# Tile1.net
KiCad netlist of a schematic drawn in Altium Designer
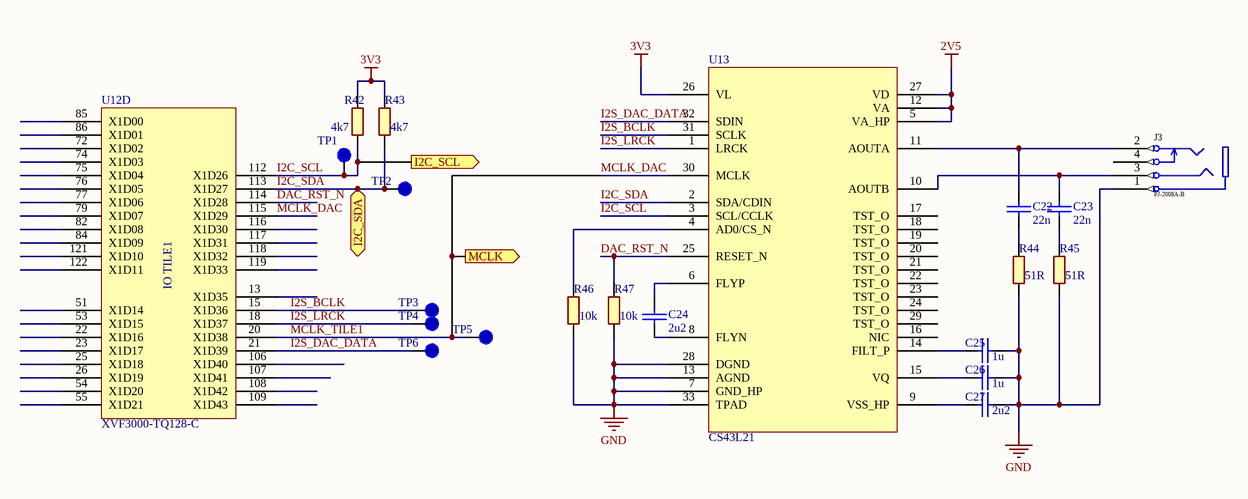
[diagram p0: Tile1.SchDoc]

(export (version "E")
  (design (tool "Eeschema 10.0.6"))
  (components
    (comp (ref "C22")
      (value "22n")
      (footprint "C0603")
      (description "Capacitor")
      (libsource (lib "Library") (part "CAP"))
    )
    (comp (ref "C23")
      (value "22n")
      (footprint "C0603")
      (description "Capacitor")
      (libsource (lib "Library") (part "CAP"))
    )
    (comp (ref "C24")
      (value "2u2")
      (footprint "C0603")
      (description "Capacitor")
      (libsource (lib "Library") (part "CAP"))
    )
    (comp (ref "C25")
      (value "1u")
      (footprint "C0603")
      (description "Capacitor")
      (libsource (lib "Library") (part "CAP"))
    )
    (comp (ref "C26")
      (value "1u")
      (footprint "C0603")
      (description "Capacitor")
      (libsource (lib "Library") (part "CAP"))
    )
    (comp (ref "C27")
      (value "2u2")
      (footprint "C0603")
      (description "Capacitor")
      (libsource (lib "Library") (part "CAP"))
    )
    (comp (ref "J3")
      (value "PJ-2008A-B")
      (footprint "PJ-2008A-B")
      (libsource (lib "Library") (part "PJ-2008A-B"))
    )
    (comp (ref "R42")
      (value "4k7")
      (footprint "R0603")
      (description "RES")
      (libsource (lib "Library") (part "R"))
    )
    (comp (ref "R43")
      (value "4k7")
      (footprint "R0603")
      (description "RES")
      (libsource (lib "Library") (part "R"))
    )
    (comp (ref "R44")
      (value "51R")
      (footprint "R0603")
      (description "RES")
      (libsource (lib "Library") (part "R"))
    )
    (comp (ref "R45")
      (value "51R")
      (footprint "R0603")
      (description "RES")
      (libsource (lib "Library") (part "R"))
    )
    (comp (ref "R46")
      (value "10k")
      (footprint "R0603")
      (description "RES")
      (libsource (lib "Library") (part "R"))
    )
    (comp (ref "R47")
      (value "10k")
      (footprint "R0603")
      (description "RES")
      (libsource (lib "Library") (part "R"))
    )
    (comp (ref "TP1") (value "TP") (footprint "TP1") (libsource (lib "Library") (part "TP")))
    (comp (ref "TP2") (value "TP") (footprint "TP1") (libsource (lib "Library") (part "TP")))
    (comp (ref "TP3") (value "TP") (footprint "TP1") (libsource (lib "Library") (part "TP")))
    (comp (ref "TP4") (value "TP") (footprint "TP1") (libsource (lib "Library") (part "TP")))
    (comp (ref "TP5") (value "TP") (footprint "TP1") (libsource (lib "Library") (part "TP")))
    (comp (ref "TP6") (value "TP") (footprint "TP1") (libsource (lib "Library") (part "TP")))
    (comp (ref "U12")
      (value "XVF3000-TQ128-C")
      (footprint "LQFP-128 - VSS")
      (libsource (lib "Library") (part "XVF3000-TQ128-C"))
    )
    (comp (ref "U13") (value "CS43L21") (footprint "QFN-32") (libsource (lib "Library") (part "CS43L21")))
  )
  (nets
    (net (code "1") (name "/DAC_RST_N") (class "Default")
      (node (ref "R47") (pin "2") (pinfunction "2_2") (pintype "passive"))
      (node (ref "U12") (pin "114") (pinfunction "X1D28_114") (pintype "passive"))
      (node (ref "U13") (pin "25") (pinfunction "RESET_N_25") (pintype "passive"))
    )
    (net (code "2") (name "/I2C_SCL") (class "Default")
      (node (ref "R42") (pin "1") (pinfunction "1_1") (pintype "passive"))
      (node (ref "TP1") (pin "1") (pinfunction "1_1") (pintype "passive"))
      (node (ref "U12") (pin "112") (pinfunction "X1D26_112") (pintype "passive"))
      (node (ref "U13") (pin "3") (pinfunction "SCL/CCLK_3") (pintype "passive"))
    )
    (net (code "3") (name "/I2C_SDA") (class "Default")
      (node (ref "R43") (pin "1") (pinfunction "1_1") (pintype "passive"))
      (node (ref "TP2") (pin "1") (pinfunction "1_1") (pintype "passive"))
      (node (ref "U12") (pin "113") (pinfunction "X1D27_113") (pintype "passive"))
      (node (ref "U13") (pin "2") (pinfunction "SDA/CDIN_2") (pintype "passive"))
    )
    (net (code "4") (name "/I2S_BCLK") (class "Default")
      (node (ref "TP3") (pin "1") (pinfunction "1_1") (pintype "passive"))
      (node (ref "U12") (pin "15") (pinfunction "X1D36_15") (pintype "passive"))
      (node (ref "U13") (pin "31") (pinfunction "SCLK_31") (pintype "passive"))
    )
    (net (code "5") (name "/I2S_DAC_DATA") (class "Default")
      (node (ref "TP6") (pin "1") (pinfunction "1_1") (pintype "passive"))
      (node (ref "U12") (pin "21") (pinfunction "X1D39_21") (pintype "passive"))
      (node (ref "U13") (pin "32") (pinfunction "SDIN_32") (pintype "passive"))
    )
    (net (code "6") (name "/I2S_LRCK") (class "Default")
      (node (ref "TP4") (pin "1") (pinfunction "1_1") (pintype "passive"))
      (node (ref "U12") (pin "18") (pinfunction "X1D37_18") (pintype "passive"))
      (node (ref "U13") (pin "1") (pinfunction "LRCK_1") (pintype "passive"))
    )
    (net (code "7") (name "/MCLK_DAC") (class "Default")
      (node (ref "TP5") (pin "1") (pinfunction "1_1") (pintype "passive"))
      (node (ref "U12") (pin "115") (pinfunction "X1D29_115") (pintype "passive"))
      (node (ref "U12") (pin "20") (pinfunction "X1D38_20") (pintype "passive"))
      (node (ref "U13") (pin "30") (pinfunction "MCLK_30") (pintype "passive"))
    )
    (net (code "8") (name "2V5") (class "Default")
      (node (ref "U13") (pin "12") (pinfunction "VA_12") (pintype "passive"))
      (node (ref "U13") (pin "27") (pinfunction "VD_27") (pintype "passive"))
      (node (ref "U13") (pin "5") (pinfunction "VA_HP_5") (pintype "passive"))
    )
    (net (code "9") (name "3V3") (class "Default")
      (node (ref "R42") (pin "2") (pinfunction "2_2") (pintype "passive"))
      (node (ref "R43") (pin "2") (pinfunction "2_2") (pintype "passive"))
      (node (ref "U13") (pin "26") (pinfunction "VL_26") (pintype "passive"))
    )
    (net (code "10") (name "GND") (class "Default")
      (node (ref "C25") (pin "2") (pinfunction "2_2") (pintype "passive"))
      (node (ref "C26") (pin "2") (pinfunction "2_2") (pintype "passive"))
      (node (ref "C27") (pin "2") (pinfunction "2_2") (pintype "passive"))
      (node (ref "J3") (pin "1") (pintype "output"))
      (node (ref "R44") (pin "1") (pinfunction "1_1") (pintype "passive"))
      (node (ref "R45") (pin "1") (pinfunction "1_1") (pintype "passive"))
      (node (ref "R46") (pin "1") (pinfunction "1_1") (pintype "passive"))
      (node (ref "R47") (pin "1") (pinfunction "1_1") (pintype "passive"))
      (node (ref "U13") (pin "13") (pinfunction "AGND_13") (pintype "passive"))
      (node (ref "U13") (pin "28") (pinfunction "DGND_28") (pintype "passive"))
      (node (ref "U13") (pin "33") (pinfunction "TPAD_33") (pintype "passive"))
      (node (ref "U13") (pin "7") (pinfunction "GND_HP_7") (pintype "passive"))
    )
    (net (code "11") (name "Net-(C22-Pad1)") (class "Default")
      (node (ref "C22") (pin "1") (pinfunction "1_1") (pintype "passive"))
      (node (ref "R44") (pin "2") (pinfunction "2_2") (pintype "passive"))
    )
    (net (code "12") (name "Net-(C23-Pad1)") (class "Default")
      (node (ref "C23") (pin "1") (pinfunction "1_1") (pintype "passive"))
      (node (ref "R45") (pin "2") (pinfunction "2_2") (pintype "passive"))
    )
    (net (code "13") (name "Net-(U13-AD0{slash}CS_N)") (class "Default")
      (node (ref "R46") (pin "2") (pinfunction "2_2") (pintype "passive"))
      (node (ref "U13") (pin "4") (pinfunction "AD0/CS_N_4") (pintype "passive"))
    )
    (net (code "14") (name "Net-(U13-AOUTA)") (class "Default")
      (node (ref "C22") (pin "2") (pinfunction "2_2") (pintype "passive"))
      (node (ref "J3") (pin "2") (pintype "output"))
      (node (ref "U13") (pin "11") (pinfunction "AOUTA_11") (pintype "passive"))
    )
    (net (code "15") (name "Net-(U13-AOUTB)") (class "Default")
      (node (ref "C23") (pin "2") (pinfunction "2_2") (pintype "passive"))
      (node (ref "J3") (pin "3") (pintype "output"))
      (node (ref "U13") (pin "10") (pinfunction "AOUTB_10") (pintype "passive"))
    )
    (net (code "16") (name "Net-(U13-FILT_P)") (class "Default")
      (node (ref "C25") (pin "1") (pinfunction "1_1") (pintype "passive"))
      (node (ref "U13") (pin "14") (pinfunction "FILT_P_14") (pintype "passive"))
    )
    (net (code "17") (name "Net-(U13-FLYN)") (class "Default")
      (node (ref "C24") (pin "2") (pinfunction "2_2") (pintype "passive"))
      (node (ref "U13") (pin "8") (pinfunction "FLYN_8") (pintype "passive"))
    )
    (net (code "18") (name "Net-(U13-FLYP)") (class "Default")
      (node (ref "C24") (pin "1") (pinfunction "1_1") (pintype "passive"))
      (node (ref "U13") (pin "6") (pinfunction "FLYP_6") (pintype "passive"))
    )
    (net (code "19") (name "Net-(U13-VQ)") (class "Default")
      (node (ref "C26") (pin "1") (pinfunction "1_1") (pintype "passive"))
      (node (ref "U13") (pin "15") (pinfunction "VQ_15") (pintype "passive"))
    )
    (net (code "20") (name "Net-(U13-VSS_HP)") (class "Default")
      (node (ref "C27") (pin "1") (pinfunction "1_1") (pintype "passive"))
      (node (ref "U13") (pin "9") (pinfunction "VSS_HP_9") (pintype "passive"))
    )
    (net (code "21") (name "unconnected-(J3-Pad4)") (class "Default")
      (node (ref "J3") (pin "4") (pintype "output"))
    )
    (net (code "22") (name "unconnected-(U12D-X1D00-Pad85)") (class "Default")
      (node (ref "U12") (pin "85") (pinfunction "X1D00_85") (pintype "passive"))
    )
    (net (code "23") (name "unconnected-(U12D-X1D01-Pad86)") (class "Default")
      (node (ref "U12") (pin "86") (pinfunction "X1D01_86") (pintype "passive"))
    )
    (net (code "24") (name "unconnected-(U12D-X1D02-Pad72)") (class "Default")
      (node (ref "U12") (pin "72") (pinfunction "X1D02_72") (pintype "passive"))
    )
    (net (code "25") (name "unconnected-(U12D-X1D03-Pad74)") (class "Default")
      (node (ref "U12") (pin "74") (pinfunction "X1D03_74") (pintype "passive"))
    )
    (net (code "26") (name "unconnected-(U12D-X1D04-Pad75)") (class "Default")
      (node (ref "U12") (pin "75") (pinfunction "X1D04_75") (pintype "passive"))
    )
    (net (code "27") (name "unconnected-(U12D-X1D05-Pad76)") (class "Default")
      (node (ref "U12") (pin "76") (pinfunction "X1D05_76") (pintype "passive"))
    )
    (net (code "28") (name "unconnected-(U12D-X1D06-Pad77)") (class "Default")
      (node (ref "U12") (pin "77") (pinfunction "X1D06_77") (pintype "passive"))
    )
    (net (code "29") (name "unconnected-(U12D-X1D07-Pad79)") (class "Default")
      (node (ref "U12") (pin "79") (pinfunction "X1D07_79") (pintype "passive"))
    )
    (net (code "30") (name "unconnected-(U12D-X1D08-Pad82)") (class "Default")
      (node (ref "U12") (pin "82") (pinfunction "X1D08_82") (pintype "passive"))
    )
    (net (code "31") (name "unconnected-(U12D-X1D09-Pad84)") (class "Default")
      (node (ref "U12") (pin "84") (pinfunction "X1D09_84") (pintype "passive"))
    )
    (net (code "32") (name "unconnected-(U12D-X1D10-Pad121)") (class "Default")
      (node (ref "U12") (pin "121") (pinfunction "X1D10_121") (pintype "passive"))
    )
    (net (code "33") (name "unconnected-(U12D-X1D11-Pad122)") (class "Default")
      (node (ref "U12") (pin "122") (pinfunction "X1D11_122") (pintype "passive"))
    )
    (net (code "34") (name "unconnected-(U12D-X1D14-Pad51)") (class "Default")
      (node (ref "U12") (pin "51") (pinfunction "X1D14_51") (pintype "passive"))
    )
    (net (code "35") (name "unconnected-(U12D-X1D15-Pad53)") (class "Default")
      (node (ref "U12") (pin "53") (pinfunction "X1D15_53") (pintype "passive"))
    )
    (net (code "36") (name "unconnected-(U12D-X1D16-Pad22)") (class "Default")
      (node (ref "U12") (pin "22") (pinfunction "X1D16_22") (pintype "passive"))
    )
    (net (code "37") (name "unconnected-(U12D-X1D17-Pad23)") (class "Default")
      (node (ref "U12") (pin "23") (pinfunction "X1D17_23") (pintype "passive"))
    )
    (net (code "38") (name "unconnected-(U12D-X1D18-Pad25)") (class "Default")
      (node (ref "U12") (pin "25") (pinfunction "X1D18_25") (pintype "passive"))
    )
    (net (code "39") (name "unconnected-(U12D-X1D19-Pad26)") (class "Default")
      (node (ref "U12") (pin "26") (pinfunction "X1D19_26") (pintype "passive"))
    )
    (net (code "40") (name "unconnected-(U12D-X1D20-Pad54)") (class "Default")
      (node (ref "U12") (pin "54") (pinfunction "X1D20_54") (pintype "passive"))
    )
    (net (code "41") (name "unconnected-(U12D-X1D21-Pad55)") (class "Default")
      (node (ref "U12") (pin "55") (pinfunction "X1D21_55") (pintype "passive"))
    )
    (net (code "42") (name "unconnected-(U12D-X1D30-Pad116)") (class "Default")
      (node (ref "U12") (pin "116") (pinfunction "X1D30_116") (pintype "passive"))
    )
    (net (code "43") (name "unconnected-(U12D-X1D31-Pad117)") (class "Default")
      (node (ref "U12") (pin "117") (pinfunction "X1D31_117") (pintype "passive"))
    )
    (net (code "44") (name "unconnected-(U12D-X1D32-Pad118)") (class "Default")
      (node (ref "U12") (pin "118") (pinfunction "X1D32_118") (pintype "passive"))
    )
    (net (code "45") (name "unconnected-(U12D-X1D33-Pad119)") (class "Default")
      (node (ref "U12") (pin "119") (pinfunction "X1D33_119") (pintype "passive"))
    )
    (net (code "46") (name "unconnected-(U12D-X1D35-Pad13)") (class "Default")
      (node (ref "U12") (pin "13") (pinfunction "X1D35_13") (pintype "passive"))
    )
    (net (code "47") (name "unconnected-(U12D-X1D40-Pad106)") (class "Default")
      (node (ref "U12") (pin "106") (pinfunction "X1D40_106") (pintype "passive"))
    )
    (net (code "48") (name "unconnected-(U12D-X1D41-Pad107)") (class "Default")
      (node (ref "U12") (pin "107") (pinfunction "X1D41_107") (pintype "passive"))
    )
    (net (code "49") (name "unconnected-(U12D-X1D42-Pad108)") (class "Default")
      (node (ref "U12") (pin "108") (pinfunction "X1D42_108") (pintype "passive"))
    )
    (net (code "50") (name "unconnected-(U12D-X1D43-Pad109)") (class "Default")
      (node (ref "U12") (pin "109") (pinfunction "X1D43_109") (pintype "passive"))
    )
    (net (code "51") (name "unconnected-(U13-NIC-Pad16)") (class "Default")
      (node (ref "U13") (pin "16") (pinfunction "NIC_16") (pintype "passive"))
    )
    (net (code "52") (name "unconnected-(U13-TST_O-Pad17)") (class "Default")
      (node (ref "U13") (pin "17") (pinfunction "TST_O_17") (pintype "passive"))
    )
    (net (code "53") (name "unconnected-(U13-TST_O-Pad18)") (class "Default")
      (node (ref "U13") (pin "18") (pinfunction "TST_O_18") (pintype "passive"))
    )
    (net (code "54") (name "unconnected-(U13-TST_O-Pad19)") (class "Default")
      (node (ref "U13") (pin "19") (pinfunction "TST_O_19") (pintype "passive"))
    )
    (net (code "55") (name "unconnected-(U13-TST_O-Pad20)") (class "Default")
      (node (ref "U13") (pin "20") (pinfunction "TST_O_20") (pintype "passive"))
    )
    (net (code "56") (name "unconnected-(U13-TST_O-Pad21)") (class "Default")
      (node (ref "U13") (pin "21") (pinfunction "TST_O_21") (pintype "passive"))
    )
    (net (code "57") (name "unconnected-(U13-TST_O-Pad22)") (class "Default")
      (node (ref "U13") (pin "22") (pinfunction "TST_O_22") (pintype "passive"))
    )
    (net (code "58") (name "unconnected-(U13-TST_O-Pad23)") (class "Default")
      (node (ref "U13") (pin "23") (pinfunction "TST_O_23") (pintype "passive"))
    )
    (net (code "59") (name "unconnected-(U13-TST_O-Pad24)") (class "Default")
      (node (ref "U13") (pin "24") (pinfunction "TST_O_24") (pintype "passive"))
    )
    (net (code "60") (name "unconnected-(U13-TST_O-Pad29)") (class "Default")
      (node (ref "U13") (pin "29") (pinfunction "TST_O_29") (pintype "passive"))
    )
  )
)
